# tmp235_Front_End_Siognal_Chain.net
KiCad netlist of a schematic drawn in Altium Designer
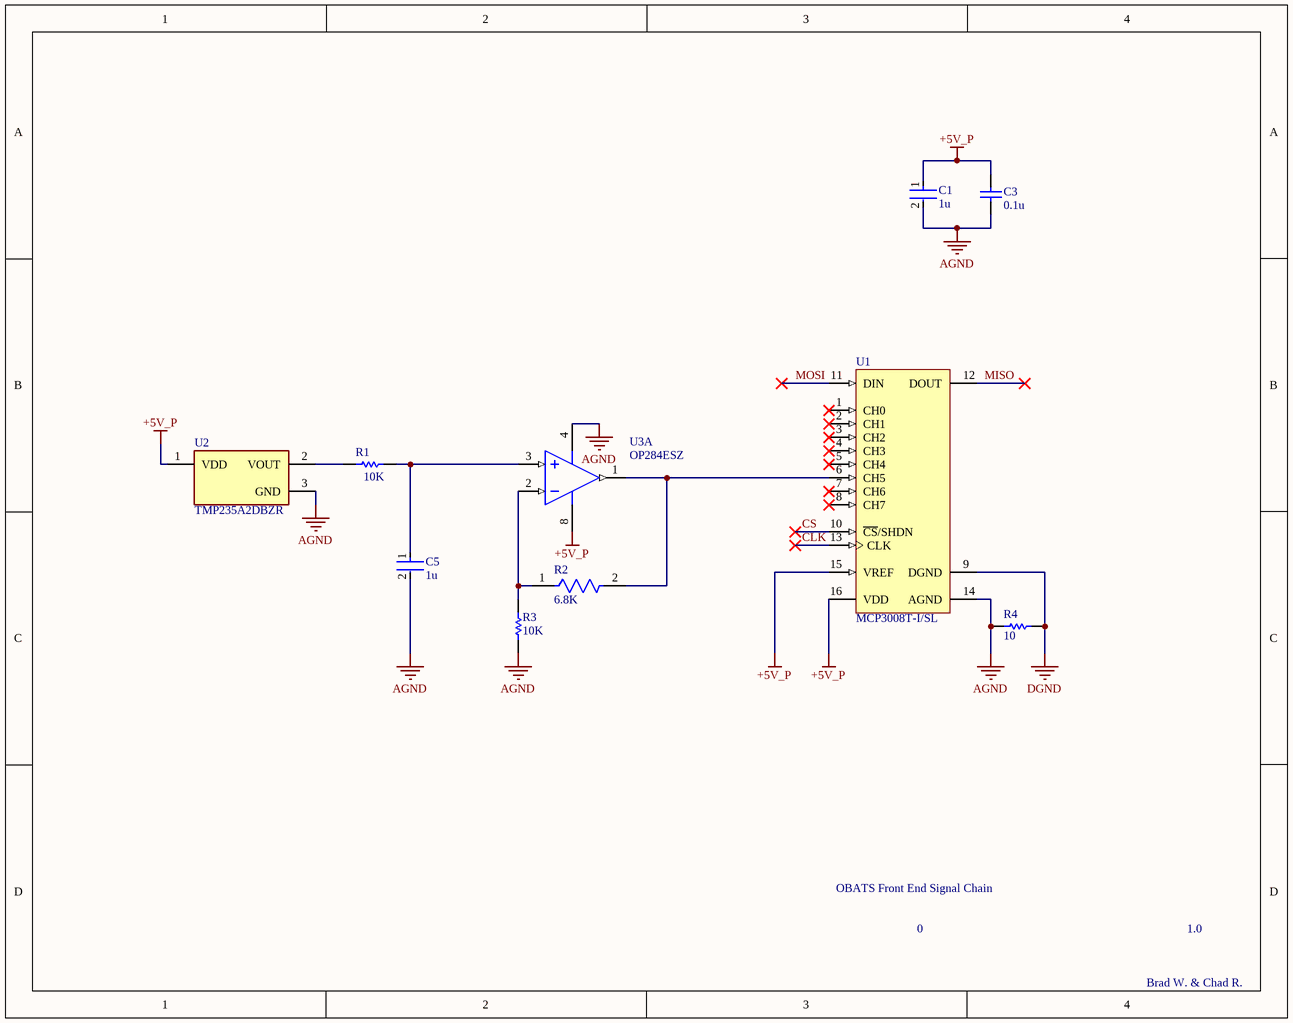
[diagram p0: tmp235_Front_End_Siognal_Chain.SchDoc]

(export (version "E")
  (design (tool "Eeschema 10.0.6"))
  (components
    (comp (ref "C1")
      (value "1u")
      (footprint "FP-CL31-IPC_B")
      (description "Cap Ceramic 1uF 50V X7R ±10% SMD 1206 +125°C Embossed T/R")
      (fields (field (name "VOLTAGE") "50V") (field (name "TOLERANCE") "10%"))
      (libsource (lib "Altium Content Vault") (part "b4654b650e69147ec39a6b967a45e02"))
    )
    (comp (ref "C3")
      (value "0.1u")
      (footprint "CAPC1206(3216)130_M")
      (description "CAP 100nF 100V ±20% 1206 (3216 Metric) Thickness 1.3mm SMD")
      (fields (field (name "TOLERANCE") "Â±20%"))
      (libsource (lib "Altium Content Vault") (part "CAP"))
    )
    (comp (ref "C5")
      (value "1u")
      (footprint "FP-CL31-IPC_B")
      (description "Cap Ceramic 1uF 50V X7R ±10% SMD 1206 +125°C Embossed T/R")
      (fields (field (name "VOLTAGE") "50V") (field (name "TOLERANCE") "10%"))
      (libsource (lib "Altium Content Vault") (part "b4654b650e69147ec39a6b967a45e02"))
    )
    (comp (ref "R1")
      (value "10K")
      (footprint "RESC3116X65X45ML10T20")
      (fields (field (name "MANUFACTURER") "Yageo") (field (name "PART NUMBER") "AC1206FR-0710KL"))
      (libsource (lib "Altium Content Vault") (part "RES"))
    )
    (comp (ref "R2")
      (value "6.8K")
      (footprint "FP-AC1206-MFG")
      (description "RES SMD 6.8K OHM 1% 1/4W 1206")
      (fields
        (field (name "OCTOPART") "https://octopart.com/ac1206fr-076k8l-yageo-26041203")
        (field (name "MANUFACTURER PART NUMBER") "AC1206FR-076K8L")
      )
      (libsource (lib "Altium Content Vault") (part "1029c3af85768c4190bb7ad29bc67b5"))
    )
    (comp (ref "R3")
      (value "10K")
      (footprint "RESC3116X65X45ML10T20")
      (fields (field (name "MANUFACTURER") "Yageo") (field (name "PART NUMBER") "AC1206FR-0710KL"))
      (libsource (lib "Altium Content Vault") (part "RES"))
    )
    (comp (ref "R4")
      (value "10")
      (footprint "RESC3216X60X45ML10T20")
      (fields (field (name "MANUFACTURER") "Vishay Dale") (field (name "PART NUMBER") "CRCW120610R0FKEA"))
      (libsource (lib "Altium Content Vault") (part "RES"))
    )
    (comp (ref "U1")
      (value "MCP3008T-I/SL")
      (footprint "SOIC-SL16_N")
      (libsource (lib "Altium Content Vault") (part "CON-ADC-MCP3008-16"))
    )
    (comp (ref "U2")
      (value "TMP235A2DBZR")
      (footprint "FP-DBZ0003A-MFG")
      (description "LOW-POWER HIGH-ACCURACY ANALOG O")
      (fields
        (field (name "MANUFACTURER") "Texas Instruments")
        (field (name "OCTOPART") "https://octopart.com/tmp235a2dbzr-texas+instruments-94966376")
      )
      (libsource (lib "Altium Content Vault") (part "1212246baba8f64ab0dd7b63bd818eb"))
    )
    (comp (ref "U3")
      (value "OP284ESZ")
      (footprint "ADI-R-8_L")
      (fields (field (name "GENERIC PART NUMBER") "OP284") (field (name "MANUFACTURER") "Analog Devices"))
      (libsource (lib "Altium Content Vault") (part "ADI-OP29X-R-8"))
    )
  )
  (nets
    (net (code "1") (name "+5V_P") (class "Default")
      (node (ref "C1") (pin "1") (pinfunction "1_1") (pintype "passive"))
      (node (ref "C3") (pin "2") (pinfunction "2_2") (pintype "passive"))
      (node (ref "U1") (pin "15") (pinfunction "VREF_15") (pintype "input"))
      (node (ref "U1") (pin "16") (pinfunction "VDD_16") (pintype "power_in"))
      (node (ref "U2") (pin "1") (pinfunction "VDD_1") (pintype "power_in"))
      (node (ref "U3") (pin "8") (pinfunction "+V_8") (pintype "power_in"))
    )
    (net (code "2") (name "/CLK") (class "Default")
      (node (ref "U1") (pin "13") (pinfunction "CLK_13") (pintype "input+no_connect"))
    )
    (net (code "3") (name "/CS") (class "Default")
      (node (ref "U1") (pin "10") (pinfunction "~{CS}/SHDN_10") (pintype "input+no_connect"))
    )
    (net (code "4") (name "/MISO") (class "Default")
      (node (ref "U1") (pin "12") (pinfunction "DOUT_12") (pintype "tri_state+no_connect"))
    )
    (net (code "5") (name "/MOSI") (class "Default")
      (node (ref "U1") (pin "11") (pinfunction "DIN_11") (pintype "input+no_connect"))
    )
    (net (code "6") (name "AGND") (class "Default")
      (node (ref "C1") (pin "2") (pinfunction "2_2") (pintype "passive"))
      (node (ref "C3") (pin "1") (pinfunction "1_1") (pintype "passive"))
      (node (ref "C5") (pin "2") (pinfunction "2_2") (pintype "passive"))
      (node (ref "R3") (pin "1") (pinfunction "1_1") (pintype "passive"))
      (node (ref "R4") (pin "1") (pinfunction "1_1") (pintype "passive"))
      (node (ref "U1") (pin "14") (pinfunction "AGND_14") (pintype "power_in"))
      (node (ref "U2") (pin "3") (pinfunction "GND_3") (pintype "power_in"))
      (node (ref "U3") (pin "4") (pinfunction "-V_4") (pintype "power_in"))
    )
    (net (code "7") (name "DGND") (class "Default")
      (node (ref "R4") (pin "2") (pinfunction "2_2") (pintype "passive"))
      (node (ref "U1") (pin "9") (pinfunction "DGND_9") (pintype "power_in"))
    )
    (net (code "8") (name "Net-(U1-CH5)") (class "Default")
      (node (ref "R2") (pin "2") (pinfunction "2_2") (pintype "passive"))
      (node (ref "U1") (pin "6") (pinfunction "CH5_6") (pintype "input"))
      (node (ref "U3") (pin "1") (pinfunction "OUT_A_1") (pintype "output"))
    )
    (net (code "9") (name "Net-(U2-VOUT)") (class "Default")
      (node (ref "R1") (pin "1") (pinfunction "1_1") (pintype "passive"))
      (node (ref "U2") (pin "2") (pinfunction "VOUT_2") (pintype "passive"))
    )
    (net (code "10") (name "Net-(U3A-+IN_A)") (class "Default")
      (node (ref "C5") (pin "1") (pinfunction "1_1") (pintype "passive"))
      (node (ref "R1") (pin "2") (pinfunction "2_2") (pintype "passive"))
      (node (ref "U3") (pin "3") (pinfunction "+IN_A_3") (pintype "input"))
    )
    (net (code "11") (name "Net-(U3A--IN_A)") (class "Default")
      (node (ref "R2") (pin "1") (pinfunction "1_1") (pintype "passive"))
      (node (ref "R3") (pin "2") (pinfunction "2_2") (pintype "passive"))
      (node (ref "U3") (pin "2") (pinfunction "-IN_A_2") (pintype "input"))
    )
    (net (code "12") (name "unconnected-(U1-CH0-Pad1)") (class "Default")
      (node (ref "U1") (pin "1") (pinfunction "CH0_1") (pintype "input+no_connect"))
    )
    (net (code "13") (name "unconnected-(U1-CH1-Pad2)") (class "Default")
      (node (ref "U1") (pin "2") (pinfunction "CH1_2") (pintype "input+no_connect"))
    )
    (net (code "14") (name "unconnected-(U1-CH2-Pad3)") (class "Default")
      (node (ref "U1") (pin "3") (pinfunction "CH2_3") (pintype "input+no_connect"))
    )
    (net (code "15") (name "unconnected-(U1-CH3-Pad4)") (class "Default")
      (node (ref "U1") (pin "4") (pinfunction "CH3_4") (pintype "input+no_connect"))
    )
    (net (code "16") (name "unconnected-(U1-CH4-Pad5)") (class "Default")
      (node (ref "U1") (pin "5") (pinfunction "CH4_5") (pintype "input+no_connect"))
    )
    (net (code "17") (name "unconnected-(U1-CH6-Pad7)") (class "Default")
      (node (ref "U1") (pin "7") (pinfunction "CH6_7") (pintype "input+no_connect"))
    )
    (net (code "18") (name "unconnected-(U1-CH7-Pad8)") (class "Default")
      (node (ref "U1") (pin "8") (pinfunction "CH7_8") (pintype "input+no_connect"))
    )
  )
)
